# 105358-3SC002-01-A_IR.net
KiCad netlist of a schematic drawn in Altium Designer
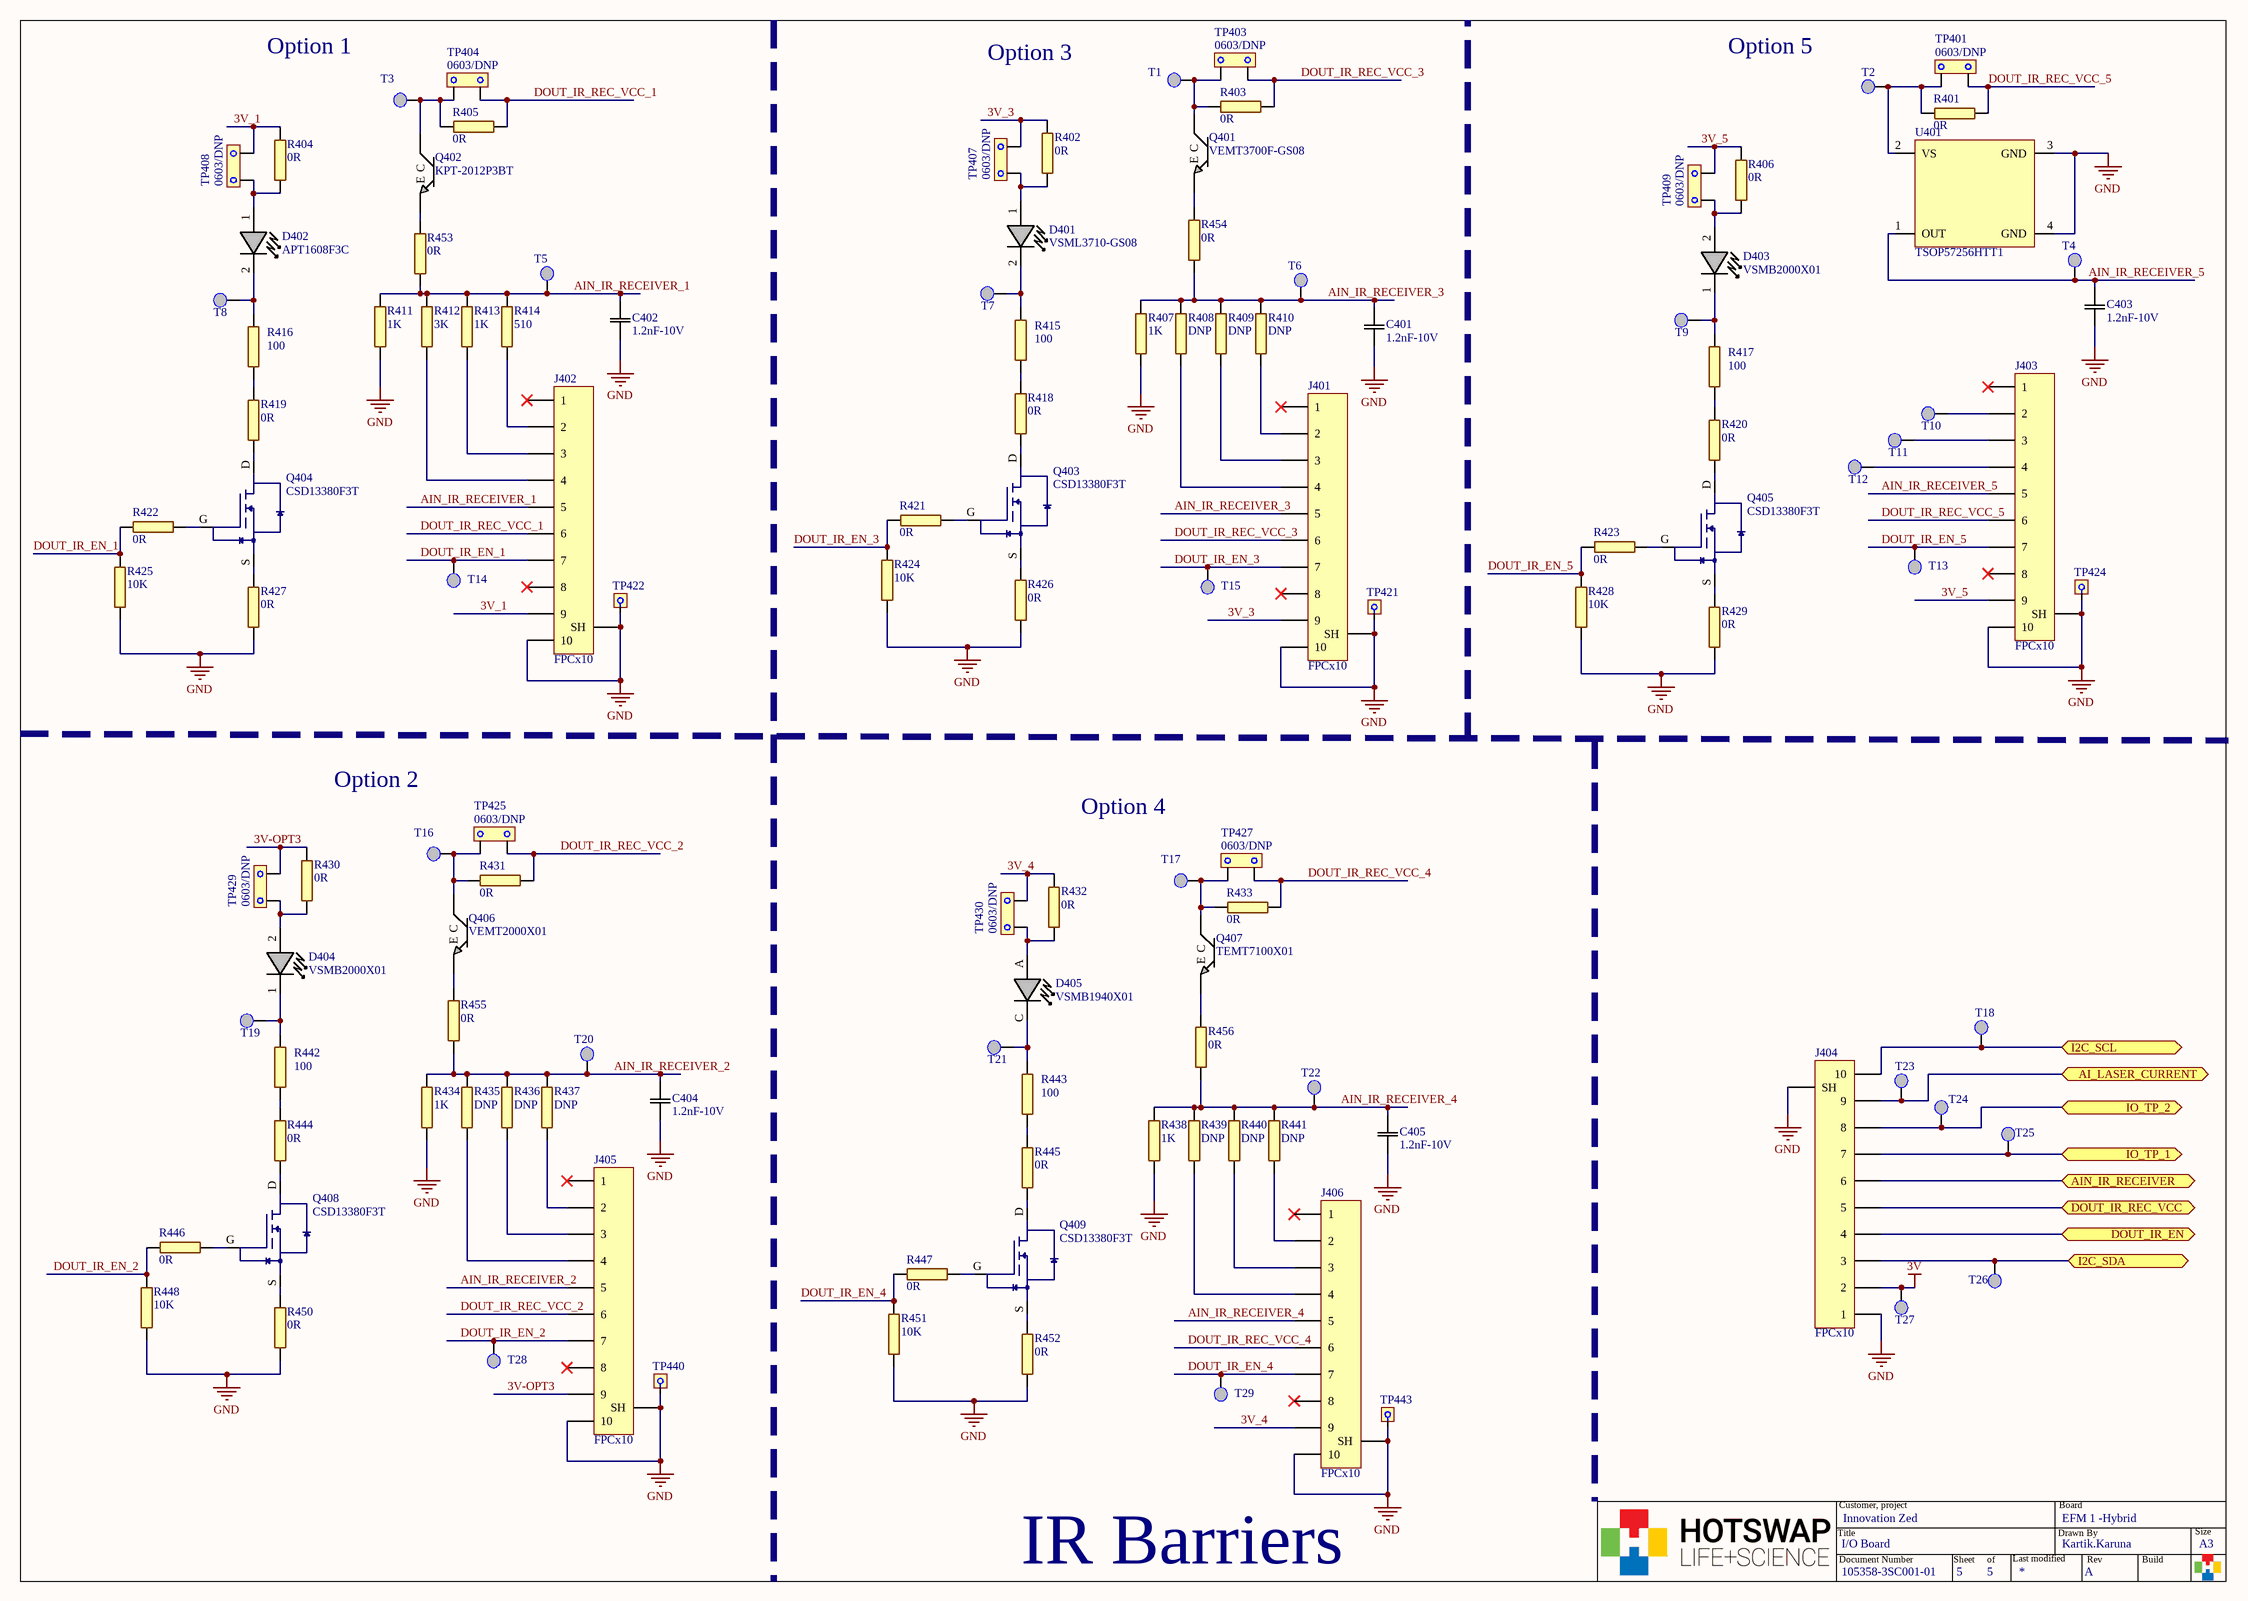
[diagram p0: 105358-3SC002-01-A_IR.SchDoc]

(export (version "E")
  (design (tool "Eeschema 10.0.6"))
  (components
    (comp (ref "C401")
      (value "1.2nF-10V")
      (footprint "0402C_HIGH_DENSITY")
      (description "1.2nF ±10% 10V U2J Ceramic Capacitor 0402")
      (fields
        (field (name "MANUFACTURER PART NUMBER") "GRM1557U1A122JA01D")
        (field (name "MANUFACTURER") "Murata Electronics North America")
      )
      (libsource (lib "ConnectMedical") (part "0402C-1.2nF-10V"))
    )
    (comp (ref "C402")
      (value "1.2nF-10V")
      (footprint "0402C_HIGH_DENSITY")
      (description "1.2nF ±10% 10V U2J Ceramic Capacitor 0402")
      (fields
        (field (name "MANUFACTURER PART NUMBER") "GRM1557U1A122JA01D")
        (field (name "MANUFACTURER") "Murata Electronics North America")
      )
      (libsource (lib "ConnectMedical") (part "0402C-1.2nF-10V"))
    )
    (comp (ref "C403")
      (value "1.2nF-10V")
      (footprint "0402C_HIGH_DENSITY")
      (description "1.2nF ±10% 10V U2J Ceramic Capacitor 0402")
      (fields
        (field (name "MANUFACTURER PART NUMBER") "GRM1557U1A122JA01D")
        (field (name "MANUFACTURER") "Murata Electronics North America")
      )
      (libsource (lib "ConnectMedical") (part "0402C-1.2nF-10V"))
    )
    (comp (ref "C404")
      (value "1.2nF-10V")
      (footprint "0402C_HIGH_DENSITY")
      (description "1.2nF ±10% 10V U2J Ceramic Capacitor 0402")
      (fields
        (field (name "MANUFACTURER PART NUMBER") "GRM1557U1A122JA01D")
        (field (name "MANUFACTURER") "Murata Electronics North America")
      )
      (libsource (lib "ConnectMedical") (part "0402C-1.2nF-10V"))
    )
    (comp (ref "C405")
      (value "1.2nF-10V")
      (footprint "0402C_HIGH_DENSITY")
      (description "1.2nF ±10% 10V U2J Ceramic Capacitor 0402")
      (fields
        (field (name "MANUFACTURER PART NUMBER") "GRM1557U1A122JA01D")
        (field (name "MANUFACTURER") "Murata Electronics North America")
      )
      (libsource (lib "ConnectMedical") (part "0402C-1.2nF-10V"))
    )
    (comp (ref "D401")
      (value "VSML3710-GS08")
      (footprint "VSML3710-GS08")
      (description "EMITTER IR 940NM 100MA PLCC")
      (fields
        (field (name "MANUFACTURER") "Vishay Semiconductor Opto Division")
        (field (name "DIGI-KEY PART NUMBER") "751-1257-1-ND")
      )
      (libsource (lib "ConnectMedical") (part "VSML3710-GS08"))
    )
    (comp (ref "D402")
      (value "APT1608F3C")
      (footprint "APT1608F3C")
      (description "0603 INFRARED DIODE")
      (fields
        (field (name "MANUFACTURER") "Kingbright")
        (field (name "DIGI-KEY PART NUMBER") "754-1433-1-ND")
      )
      (libsource (lib "ConnectMedical") (part "APT1608F3C"))
    )
    (comp (ref "D403")
      (value "VSMB2000X01")
      (footprint "SODFL580X160")
      (description "EMITTER IR 940NM 100MA SMD")
      (fields
        (field (name "MANUFACTURER") "Vishay Semiconductor Opto Division")
        (field (name "DIGI-KEY PART NUMBER") "VSMB2000X01CT-ND")
      )
      (libsource (lib "ConnectMedical") (part "VSMB2000X01"))
    )
    (comp (ref "D404")
      (value "VSMB2000X01")
      (footprint "SODFL580X160")
      (description "EMITTER IR 940NM 100MA SMD")
      (fields
        (field (name "MANUFACTURER") "Vishay Semiconductor Opto Division")
        (field (name "DIGI-KEY PART NUMBER") "VSMB2000X01CT-ND")
      )
      (libsource (lib "ConnectMedical") (part "VSMB2000X01"))
    )
    (comp (ref "D405")
      (value "VSMB1940X01")
      (footprint "VSMB1940X01")
      (description "EMITTER IR 940NM 100MA 0805")
      (fields
        (field (name "MANUFACTURER") "Vishay Semiconductor Opto Division")
        (field (name "DIGI-KEY PART NUMBER") "VSMB1940X01CT-ND")
      )
      (libsource (lib "ConnectMedical") (part "VSMB1940X01"))
    )
    (comp (ref "J401")
      (value "FPCx10")
      (footprint "FPCx10-5034801000")
      (description "CONN FFC FPC 10POS 0.50MM R/A")
      (fields
        (field (name "MANUFACTURER PART NUMBER") "5034801000")
        (field (name "MANUFACTURER") "Molex, LLC")
      )
      (libsource (lib "") (part "FPCx10_1"))
    )
    (comp (ref "J402")
      (value "FPCx10")
      (footprint "FPCx10-5034801000")
      (description "CONN FFC FPC 10POS 0.50MM R/A")
      (fields
        (field (name "MANUFACTURER PART NUMBER") "5034801000")
        (field (name "MANUFACTURER") "Molex, LLC")
      )
      (libsource (lib "") (part "FPCx10_1"))
    )
    (comp (ref "J403")
      (value "FPCx10")
      (footprint "FPCx10-5034801000")
      (description "CONN FFC FPC 10POS 0.50MM R/A")
      (fields
        (field (name "MANUFACTURER PART NUMBER") "5034801000")
        (field (name "MANUFACTURER") "Molex, LLC")
      )
      (libsource (lib "") (part "FPCx10_1"))
    )
    (comp (ref "J404")
      (value "FPCx10")
      (footprint "FPCx10-5034801000")
      (description "CONN FFC FPC 10POS 0.50MM R/A")
      (fields
        (field (name "MANUFACTURER PART NUMBER") "5034801000")
        (field (name "MANUFACTURER") "Molex, LLC")
      )
      (libsource (lib "ConnectMedical") (part "FPCx10"))
    )
    (comp (ref "J405")
      (value "FPCx10")
      (footprint "FPCx10-5034801000")
      (description "CONN FFC FPC 10POS 0.50MM R/A")
      (fields
        (field (name "MANUFACTURER PART NUMBER") "5034801000")
        (field (name "MANUFACTURER") "Molex, LLC")
      )
      (libsource (lib "") (part "FPCx10_1"))
    )
    (comp (ref "J406")
      (value "FPCx10")
      (footprint "FPCx10-5034801000")
      (description "CONN FFC FPC 10POS 0.50MM R/A")
      (fields
        (field (name "MANUFACTURER PART NUMBER") "5034801000")
        (field (name "MANUFACTURER") "Molex, LLC")
      )
      (libsource (lib "") (part "FPCx10_1"))
    )
    (comp (ref "Q401")
      (value "VEMT3700F-GS08")
      (footprint "VEMT3700F-GS08")
      (description "PHOTO TRANS. SMD PLCC2")
      (fields
        (field (name "MANUFACTURER") "Vishay Semiconductor Opto Division")
        (field (name "DIGI-KEY PART NUMBER") "VEMT3700F-GS08CT-ND")
      )
      (libsource (lib "ConnectMedical") (part "VEMT3700F-GS08"))
    )
    (comp (ref "Q402")
      (value "KPT-2012P3BT")
      (footprint "APT2012P3BT")
      (description "0805 PHOTOTRANSISTOR")
      (fields
        (field (name "MANUFACTURER") "Kingbright")
        (field (name "DIGI-KEY PART NUMBER") "754-1436-1-ND")
      )
      (libsource (lib "ConnectMedical") (part "APT2012P3BT"))
    )
    (comp (ref "Q403")
      (value "CSD13380F3T")
      (footprint "CSD13380F3-DFN40P69X35-3L")
      (description "12V N-CHANNEL FEMTOFET MOSFET")
      (fields (field (name "MANUFACTURER") "Texas Instruments"))
      (libsource (lib "ConnectMedical") (part "CSD13380F3T"))
    )
    (comp (ref "Q404")
      (value "CSD13380F3T")
      (footprint "CSD13380F3-DFN40P69X35-3L")
      (description "12V N-CHANNEL FEMTOFET MOSFET")
      (fields (field (name "MANUFACTURER") "Texas Instruments"))
      (libsource (lib "ConnectMedical") (part "CSD13380F3T"))
    )
    (comp (ref "Q405")
      (value "CSD13380F3T")
      (footprint "CSD13380F3-DFN40P69X35-3L")
      (description "12V N-CHANNEL FEMTOFET MOSFET")
      (fields (field (name "MANUFACTURER") "Texas Instruments"))
      (libsource (lib "ConnectMedical") (part "CSD13380F3T"))
    )
    (comp (ref "Q406")
      (value "VEMT2000X01")
      (footprint "SODFL580X160")
      (description "PHOTOTRANSISTOR NPN REV GULLWING")
      (fields
        (field (name "MANUFACTURER") "Vishay Semiconductor Opto Division")
        (field (name "DIGI-KEY PART NUMBER") "VEMT2000X01CT-ND")
      )
      (libsource (lib "ConnectMedical") (part "VEMT2000X01"))
    )
    (comp (ref "Q407")
      (value "TEMT7100X01")
      (footprint "TEMT7100X01")
      (description "PHOTOTRANSISTOR 870NM 0805 SMD")
      (fields
        (field (name "MANUFACTURER") "Vishay Semiconductor Opto Division")
        (field (name "DIGI-KEY PART NUMBER") "TEMT7100X01CT-ND")
      )
      (libsource (lib "ConnectMedical") (part "TEMT7100X01"))
    )
    (comp (ref "Q408")
      (value "CSD13380F3T")
      (footprint "CSD13380F3-DFN40P69X35-3L")
      (description "12V N-CHANNEL FEMTOFET MOSFET")
      (fields (field (name "MANUFACTURER") "Texas Instruments"))
      (libsource (lib "ConnectMedical") (part "CSD13380F3T"))
    )
    (comp (ref "Q409")
      (value "CSD13380F3T")
      (footprint "CSD13380F3-DFN40P69X35-3L")
      (description "12V N-CHANNEL FEMTOFET MOSFET")
      (fields (field (name "MANUFACTURER") "Texas Instruments"))
      (libsource (lib "ConnectMedical") (part "CSD13380F3T"))
    )
    (comp (ref "R401")
      (value "0R")
      (footprint "0603R-GENRIC")
      (description "RES SMD 0 OHM 1% 1/10W 0603")
      (fields (field (name "POWER") "0.063W"))
      (libsource (lib "ConnectMedical") (part "0603R-0R -1%-0.063W"))
    )
    (comp (ref "R402")
      (value "0R")
      (footprint "0603R-GENRIC")
      (description "RES SMD 0 OHM 1% 1/10W 0603")
      (fields (field (name "POWER") "0.063W"))
      (libsource (lib "") (part "0603R-0R -1%-0.063W_2"))
    )
    (comp (ref "R403")
      (value "0R")
      (footprint "0603R-GENRIC")
      (description "RES SMD 0 OHM 1% 1/10W 0603")
      (fields (field (name "POWER") "0.063W"))
      (libsource (lib "ConnectMedical") (part "0603R-0R -1%-0.063W"))
    )
    (comp (ref "R404")
      (value "0R")
      (footprint "0603R-GENRIC")
      (description "RES SMD 0 OHM 1% 1/10W 0603")
      (fields (field (name "POWER") "0.063W"))
      (libsource (lib "") (part "0603R-0R -1%-0.063W_2"))
    )
    (comp (ref "R405")
      (value "0R")
      (footprint "0603R-GENRIC")
      (description "RES SMD 0 OHM 1% 1/10W 0603")
      (fields (field (name "POWER") "0.063W"))
      (libsource (lib "ConnectMedical") (part "0603R-0R -1%-0.063W"))
    )
    (comp (ref "R406")
      (value "0R")
      (footprint "0603R-GENRIC")
      (description "RES SMD 0 OHM 1% 1/10W 0603")
      (fields (field (name "POWER") "0.063W"))
      (libsource (lib "") (part "0603R-0R -1%-0.063W_2"))
    )
    (comp (ref "R407")
      (value "1K")
      (footprint "0402R-GENERIC")
      (description "RES SMD 1kOHM 1% 1/16W 0402")
      (fields (field (name "TOLERANCE") "1%") (field (name "POWER") "0.063W"))
      (libsource (lib "ConnectMedical") (part "0402R-1k OHM-1%-0.063W"))
    )
    (comp (ref "R408")
      (value "DNP")
      (footprint "0603R-GENRIC")
      (description "RES 0603 DNP")
      (libsource (lib "ConnectMedical") (part "0603R_DNP"))
    )
    (comp (ref "R409")
      (value "DNP")
      (footprint "0603R-GENRIC")
      (description "RES 0603 DNP")
      (libsource (lib "ConnectMedical") (part "0603R_DNP"))
    )
    (comp (ref "R410")
      (value "DNP")
      (footprint "0603R-GENRIC")
      (description "RES 0603 DNP")
      (libsource (lib "ConnectMedical") (part "0603R_DNP"))
    )
    (comp (ref "R411")
      (value "1K")
      (footprint "0402R-GENERIC")
      (description "RES SMD 1kOHM 1% 1/16W 0402")
      (fields (field (name "TOLERANCE") "1%") (field (name "POWER") "0.063W"))
      (libsource (lib "ConnectMedical") (part "0402R-1k OHM-1%-0.063W"))
    )
    (comp (ref "R412")
      (value "3K")
      (footprint "0402R-GENERIC")
      (description "RES SMD 3kOHM 1% 1/16W 0402")
      (fields (field (name "TOLERANCE") "1%") (field (name "POWER") "0.063W"))
      (libsource (lib "ConnectMedical") (part "0402R-3k OHM-1%-0.063W"))
    )
    (comp (ref "R413")
      (value "1K")
      (footprint "0402R-GENERIC")
      (description "RES SMD 1kOHM 1% 1/16W 0402")
      (fields (field (name "TOLERANCE") "1%") (field (name "POWER") "0.063W"))
      (libsource (lib "ConnectMedical") (part "0402R-1k OHM-1%-0.063W"))
    )
    (comp (ref "R414")
      (value "510")
      (footprint "0402R-GENERIC")
      (description "RES SMD 100OHM 1% 1/16W 0402")
      (fields (field (name "TOLERANCE") "1%") (field (name "POWER") "0.063W"))
      (libsource (lib "ConnectMedical") (part "0402R-500 OHM-1%-0.063W"))
    )
    (comp (ref "R415")
      (value "100")
      (footprint "0402R-GENERIC")
      (description "RES SMD 100OHM 1% 1/16W 0402")
      (fields (field (name "DIGI-KEY PART NUMBER") "311-100LRCT-ND") (field (name "MANUFACTURER") "Yageo"))
      (libsource (lib "ConnectMedical") (part "0402R-100 OHM-1%-0.063W"))
    )
    (comp (ref "R416")
      (value "100")
      (footprint "0402R-GENERIC")
      (description "RES SMD 100OHM 1% 1/16W 0402")
      (fields (field (name "DIGI-KEY PART NUMBER") "311-100LRCT-ND") (field (name "MANUFACTURER") "Yageo"))
      (libsource (lib "ConnectMedical") (part "0402R-100 OHM-1%-0.063W"))
    )
    (comp (ref "R417")
      (value "100")
      (footprint "0402R-GENERIC")
      (description "RES SMD 100OHM 1% 1/16W 0402")
      (fields (field (name "DIGI-KEY PART NUMBER") "311-100LRCT-ND") (field (name "MANUFACTURER") "Yageo"))
      (libsource (lib "ConnectMedical") (part "0402R-100 OHM-1%-0.063W"))
    )
    (comp (ref "R418")
      (value "0R")
      (footprint "0603R-GENRIC")
      (description "RES SMD 0 OHM 1% 1/10W 0603")
      (fields (field (name "POWER") "0.063W"))
      (libsource (lib "") (part "0603R-0R -1%-0.063W_1"))
    )
    (comp (ref "R419")
      (value "0R")
      (footprint "0603R-GENRIC")
      (description "RES SMD 0 OHM 1% 1/10W 0603")
      (fields (field (name "POWER") "0.063W"))
      (libsource (lib "") (part "0603R-0R -1%-0.063W_1"))
    )
    (comp (ref "R420")
      (value "0R")
      (footprint "0603R-GENRIC")
      (description "RES SMD 0 OHM 1% 1/10W 0603")
      (fields (field (name "POWER") "0.063W"))
      (libsource (lib "") (part "0603R-0R -1%-0.063W_1"))
    )
    (comp (ref "R421")
      (value "0R")
      (footprint "0603R-GENRIC")
      (description "RES SMD 0 OHM 1% 1/10W 0603")
      (fields (field (name "POWER") "0.063W"))
      (libsource (lib "ConnectMedical") (part "0603R-0R -1%-0.063W"))
    )
    (comp (ref "R422")
      (value "0R")
      (footprint "0603R-GENRIC")
      (description "RES SMD 0 OHM 1% 1/10W 0603")
      (fields (field (name "POWER") "0.063W"))
      (libsource (lib "ConnectMedical") (part "0603R-0R -1%-0.063W"))
    )
    (comp (ref "R423")
      (value "0R")
      (footprint "0603R-GENRIC")
      (description "RES SMD 0 OHM 1% 1/10W 0603")
      (fields (field (name "POWER") "0.063W"))
      (libsource (lib "ConnectMedical") (part "0603R-0R -1%-0.063W"))
    )
    (comp (ref "R424")
      (value "10K")
      (footprint "0402R-GENERIC")
      (description "RES SMD 10kOHM 1% 1/16W 0402")
      (fields (field (name "DIGI-KEY PART NUMBER") "311-10.0KLRCT-ND") (field (name "MANUFACTURER") "Yageo"))
      (libsource (lib "ConnectMedical") (part "0402R-10k OHM-1%-0.063W"))
    )
    (comp (ref "R425")
      (value "10K")
      (footprint "0402R-GENERIC")
      (description "RES SMD 10kOHM 1% 1/16W 0402")
      (fields (field (name "DIGI-KEY PART NUMBER") "311-10.0KLRCT-ND") (field (name "MANUFACTURER") "Yageo"))
      (libsource (lib "ConnectMedical") (part "0402R-10k OHM-1%-0.063W"))
    )
    (comp (ref "R426")
      (value "0R")
      (footprint "0603R-GENRIC")
      (description "RES SMD 0 OHM 1% 1/10W 0603")
      (fields (field (name "POWER") "0.063W"))
      (libsource (lib "") (part "0603R-0R -1%-0.063W_2"))
    )
    (comp (ref "R427")
      (value "0R")
      (footprint "0603R-GENRIC")
      (description "RES SMD 0 OHM 1% 1/10W 0603")
      (fields (field (name "POWER") "0.063W"))
      (libsource (lib "") (part "0603R-0R -1%-0.063W_2"))
    )
    (comp (ref "R428")
      (value "10K")
      (footprint "0402R-GENERIC")
      (description "RES SMD 10kOHM 1% 1/16W 0402")
      (fields (field (name "DIGI-KEY PART NUMBER") "311-10.0KLRCT-ND") (field (name "MANUFACTURER") "Yageo"))
      (libsource (lib "ConnectMedical") (part "0402R-10k OHM-1%-0.063W"))
    )
    (comp (ref "R429")
      (value "0R")
      (footprint "0603R-GENRIC")
      (description "RES SMD 0 OHM 1% 1/10W 0603")
      (fields (field (name "POWER") "0.063W"))
      (libsource (lib "") (part "0603R-0R -1%-0.063W_2"))
    )
    (comp (ref "R430")
      (value "0R")
      (footprint "0603R-GENRIC")
      (description "RES SMD 0 OHM 1% 1/10W 0603")
      (fields (field (name "POWER") "0.063W"))
      (libsource (lib "") (part "0603R-0R -1%-0.063W_2"))
    )
    (comp (ref "R431")
      (value "0R")
      (footprint "0603R-GENRIC")
      (description "RES SMD 0 OHM 1% 1/10W 0603")
      (fields (field (name "POWER") "0.063W"))
      (libsource (lib "ConnectMedical") (part "0603R-0R -1%-0.063W"))
    )
    (comp (ref "R432")
      (value "0R")
      (footprint "0603R-GENRIC")
      (description "RES SMD 0 OHM 1% 1/10W 0603")
      (fields (field (name "POWER") "0.063W"))
      (libsource (lib "") (part "0603R-0R -1%-0.063W_2"))
    )
    (comp (ref "R433")
      (value "0R")
      (footprint "0603R-GENRIC")
      (description "RES SMD 0 OHM 1% 1/10W 0603")
      (fields (field (name "POWER") "0.063W"))
      (libsource (lib "ConnectMedical") (part "0603R-0R -1%-0.063W"))
    )
    (comp (ref "R434")
      (value "1K")
      (footprint "0402R-GENERIC")
      (description "RES SMD 1kOHM 1% 1/16W 0402")
      (fields (field (name "TOLERANCE") "1%") (field (name "POWER") "0.063W"))
      (libsource (lib "ConnectMedical") (part "0402R-1k OHM-1%-0.063W"))
    )
    (comp (ref "R435")
      (value "DNP")
      (footprint "0603R-GENRIC")
      (description "RES 0603 DNP")
      (libsource (lib "ConnectMedical") (part "0603R_DNP"))
    )
    (comp (ref "R436")
      (value "DNP")
      (footprint "0603R-GENRIC")
      (description "RES 0603 DNP")
      (libsource (lib "ConnectMedical") (part "0603R_DNP"))
    )
    (comp (ref "R437")
      (value "DNP")
      (footprint "0603R-GENRIC")
      (description "RES 0603 DNP")
      (libsource (lib "ConnectMedical") (part "0603R_DNP"))
    )
    (comp (ref "R438")
      (value "1K")
      (footprint "0402R-GENERIC")
      (description "RES SMD 1kOHM 1% 1/16W 0402")
      (fields (field (name "TOLERANCE") "1%") (field (name "POWER") "0.063W"))
      (libsource (lib "ConnectMedical") (part "0402R-1k OHM-1%-0.063W"))
    )
    (comp (ref "R439")
      (value "DNP")
      (footprint "0603R-GENRIC")
      (description "RES 0603 DNP")
      (libsource (lib "ConnectMedical") (part "0603R_DNP"))
    )
    (comp (ref "R440")
      (value "DNP")
      (footprint "0603R-GENRIC")
      (description "RES 0603 DNP")
      (libsource (lib "ConnectMedical") (part "0603R_DNP"))
    )
    (comp (ref "R441")
      (value "DNP")
      (footprint "0603R-GENRIC")
      (description "RES 0603 DNP")
      (libsource (lib "ConnectMedical") (part "0603R_DNP"))
    )
    (comp (ref "R442")
      (value "100")
      (footprint "0402R-GENERIC")
      (description "RES SMD 100OHM 1% 1/16W 0402")
      (fields (field (name "DIGI-KEY PART NUMBER") "311-100LRCT-ND") (field (name "MANUFACTURER") "Yageo"))
      (libsource (lib "ConnectMedical") (part "0402R-100 OHM-1%-0.063W"))
    )
    (comp (ref "R443")
      (value "100")
      (footprint "0402R-GENERIC")
      (description "RES SMD 100OHM 1% 1/16W 0402")
      (fields (field (name "DIGI-KEY PART NUMBER") "311-100LRCT-ND") (field (name "MANUFACTURER") "Yageo"))
      (libsource (lib "ConnectMedical") (part "0402R-100 OHM-1%-0.063W"))
    )
    (comp (ref "R444")
      (value "0R")
      (footprint "0603R-GENRIC")
      (description "RES SMD 0 OHM 1% 1/10W 0603")
      (fields (field (name "POWER") "0.063W"))
      (libsource (lib "") (part "0603R-0R -1%-0.063W_1"))
    )
    (comp (ref "R445")
      (value "0R")
      (footprint "0603R-GENRIC")
      (description "RES SMD 0 OHM 1% 1/10W 0603")
      (fields (field (name "POWER") "0.063W"))
      (libsource (lib "") (part "0603R-0R -1%-0.063W_1"))
    )
    (comp (ref "R446")
      (value "0R")
      (footprint "0603R-GENRIC")
      (description "RES SMD 0 OHM 1% 1/10W 0603")
      (fields (field (name "POWER") "0.063W"))
      (libsource (lib "ConnectMedical") (part "0603R-0R -1%-0.063W"))
    )
    (comp (ref "R447")
      (value "0R")
      (footprint "0603R-GENRIC")
      (description "RES SMD 0 OHM 1% 1/10W 0603")
      (fields (field (name "POWER") "0.063W"))
      (libsource (lib "ConnectMedical") (part "0603R-0R -1%-0.063W"))
    )
    (comp (ref "R448")
      (value "10K")
      (footprint "0402R-GENERIC")
      (description "RES SMD 10kOHM 1% 1/16W 0402")
      (fields (field (name "DIGI-KEY PART NUMBER") "311-10.0KLRCT-ND") (field (name "MANUFACTURER") "Yageo"))
      (libsource (lib "ConnectMedical") (part "0402R-10k OHM-1%-0.063W"))
    )
    (comp (ref "R450")
      (value "0R")
      (footprint "0603R-GENRIC")
      (description "RES SMD 0 OHM 1% 1/10W 0603")
      (fields (field (name "POWER") "0.063W"))
      (libsource (lib "") (part "0603R-0R -1%-0.063W_2"))
    )
    (comp (ref "R451")
      (value "10K")
      (footprint "0402R-GENERIC")
      (description "RES SMD 10kOHM 1% 1/16W 0402")
      (fields (field (name "DIGI-KEY PART NUMBER") "311-10.0KLRCT-ND") (field (name "MANUFACTURER") "Yageo"))
      (libsource (lib "ConnectMedical") (part "0402R-10k OHM-1%-0.063W"))
    )
    (comp (ref "R452")
      (value "0R")
      (footprint "0603R-GENRIC")
      (description "RES SMD 0 OHM 1% 1/10W 0603")
      (fields (field (name "POWER") "0.063W"))
      (libsource (lib "") (part "0603R-0R -1%-0.063W_2"))
    )
    (comp (ref "R453")
      (value "0R")
      (footprint "0603R-GENRIC")
      (description "RES SMD 0 OHM 1% 1/10W 0603")
      (fields (field (name "POWER") "0.063W"))
      (libsource (lib "") (part "0603R-0R -1%-0.063W_1"))
    )
    (comp (ref "R454")
      (value "0R")
      (footprint "0603R-GENRIC")
      (description "RES SMD 0 OHM 1% 1/10W 0603")
      (fields (field (name "POWER") "0.063W"))
      (libsource (lib "") (part "0603R-0R -1%-0.063W_1"))
    )
    (comp (ref "R455")
      (value "0R")
      (footprint "0603R-GENRIC")
      (description "RES SMD 0 OHM 1% 1/10W 0603")
      (fields (field (name "POWER") "0.063W"))
      (libsource (lib "") (part "0603R-0R -1%-0.063W_1"))
    )
    (comp (ref "R456")
      (value "0R")
      (footprint "0603R-GENRIC")
      (description "RES SMD 0 OHM 1% 1/10W 0603")
      (fields (field (name "POWER") "0.063W"))
      (libsource (lib "") (part "0603R-0R -1%-0.063W_1"))
    )
    (comp (ref "T1")
      (value "TEST POINT")
      (footprint "PAD TEST POINT")
      (description "Testing Poiny")
      (libsource (lib "ConnectMedical") (part "TEST POINT"))
    )
    (comp (ref "T2")
      (value "TEST POINT")
      (footprint "PAD TEST POINT")
      (description "Testing Poiny")
      (libsource (lib "ConnectMedical") (part "TEST POINT"))
    )
    (comp (ref "T3")
      (value "TEST POINT")
      (footprint "PAD TEST POINT")
      (description "Testing Poiny")
      (libsource (lib "ConnectMedical") (part "TEST POINT"))
    )
    (comp (ref "T4")
      (value "TEST POINT")
      (footprint "PAD TEST POINT")
      (description "Testing Poiny")
      (libsource (lib "ConnectMedical") (part "TEST POINT"))
    )
    (comp (ref "T5")
      (value "TEST POINT")
      (footprint "PAD TEST POINT")
      (description "Testing Poiny")
      (libsource (lib "ConnectMedical") (part "TEST POINT"))
    )
    (comp (ref "T6")
      (value "TEST POINT")
      (footprint "PAD TEST POINT")
      (description "Testing Poiny")
      (libsource (lib "ConnectMedical") (part "TEST POINT"))
    )
    (comp (ref "T7")
      (value "TEST POINT")
      (footprint "PAD TEST POINT")
      (description "Testing Poiny")
      (libsource (lib "ConnectMedical") (part "TEST POINT"))
    )
    (comp (ref "T8")
      (value "TEST POINT")
      (footprint "PAD TEST POINT")
      (description "Testing Poiny")
      (libsource (lib "ConnectMedical") (part "TEST POINT"))
    )
    (comp (ref "T9")
      (value "TEST POINT")
      (footprint "PAD TEST POINT")
      (description "Testing Poiny")
      (libsource (lib "ConnectMedical") (part "TEST POINT"))
    )
    (comp (ref "T10")
      (value "TEST POINT")
      (footprint "PAD TEST POINT")
      (description "Testing Poiny")
      (libsource (lib "ConnectMedical") (part "TEST POINT"))
    )
    (comp (ref "T11")
      (value "TEST POINT")
      (footprint "PAD TEST POINT")
      (description "Testing Poiny")
      (libsource (lib "ConnectMedical") (part "TEST POINT"))
    )
    (comp (ref "T12")
      (value "TEST POINT")
      (footprint "PAD TEST POINT")
      (description "Testing Poiny")
      (libsource (lib "ConnectMedical") (part "TEST POINT"))
    )
    (comp (ref "T13")
      (value "TEST POINT")
      (footprint "PAD TEST POINT")
      (description "Testing Poiny")
      (libsource (lib "ConnectMedical") (part "TEST POINT"))
    )
    (comp (ref "T14")
      (value "TEST POINT")
      (footprint "PAD TEST POINT")
      (description "Testing Poiny")
      (libsource (lib "ConnectMedical") (part "TEST POINT"))
    )
    (comp (ref "T15")
      (value "TEST POINT")
      (footprint "PAD TEST POINT")
      (description "Testing Poiny")
      (libsource (lib "ConnectMedical") (part "TEST POINT"))
    )
    (comp (ref "T16")
      (value "TEST POINT")
      (footprint "PAD TEST POINT")
      (description "Testing Poiny")
      (libsource (lib "ConnectMedical") (part "TEST POINT"))
    )
    (comp (ref "T17")
      (value "TEST POINT")
      (footprint "PAD TEST POINT")
      (description "Testing Poiny")
      (libsource (lib "ConnectMedical") (part "TEST POINT"))
    )
    (comp (ref "T18")
      (value "TEST POINT")
      (footprint "PAD TEST POINT")
      (description "Testing Poiny")
      (libsource (lib "ConnectMedical") (part "TEST POINT"))
    )
    (comp (ref "T19")
      (value "TEST POINT")
      (footprint "PAD TEST POINT")
      (description "Testing Poiny")
      (libsource (lib "ConnectMedical") (part "TEST POINT"))
    )
    (comp (ref "T20")
      (value "TEST POINT")
      (footprint "PAD TEST POINT")
      (description "Testing Poiny")
      (libsource (lib "ConnectMedical") (part "TEST POINT"))
    )
    (comp (ref "T21")
      (value "TEST POINT")
      (footprint "PAD TEST POINT")
      (description "Testing Poiny")
      (libsource (lib "ConnectMedical") (part "TEST POINT"))
    )
    (comp (ref "T22")
      (value "TEST POINT")
      (footprint "PAD TEST POINT")
      (description "Testing Poiny")
      (libsource (lib "ConnectMedical") (part "TEST POINT"))
    )
    (comp (ref "T23")
      (value "TEST POINT")
      (footprint "PAD TEST POINT")
      (description "Testing Poiny")
      (libsource (lib "ConnectMedical") (part "TEST POINT"))
    )
    (comp (ref "T24")
      (value "TEST POINT")
      (footprint "PAD TEST POINT")
      (description "Testing Poiny")
      (libsource (lib "ConnectMedical") (part "TEST POINT"))
    )
    (comp (ref "T25")
      (value "TEST POINT")
      (footprint "PAD TEST POINT")
      (description "Testing Poiny")
      (libsource (lib "ConnectMedical") (part "TEST POINT"))
    )
    (comp (ref "T26")
      (value "TEST POINT")
      (footprint "PAD TEST POINT")
      (description "Testing Poiny")
      (libsource (lib "ConnectMedical") (part "TEST POINT"))
    )
    (comp (ref "T27")
      (value "TEST POINT")
      (footprint "PAD TEST POINT")
      (description "Testing Poiny")
      (libsource (lib "ConnectMedical") (part "TEST POINT"))
    )
    (comp (ref "T28")
      (value "TEST POINT")
      (footprint "PAD TEST POINT")
      (description "Testing Poiny")
      (libsource (lib "ConnectMedical") (part "TEST POINT"))
    )
    (comp (ref "T29")
      (value "TEST POINT")
      (footprint "PAD TEST POINT")
      (description "Testing Poiny")
      (libsource (lib "ConnectMedical") (part "TEST POINT"))
    )
    (comp (ref "TP401")
      (value "0603/DNP")
      (footprint "TESTPOINT_C_R0608")
      (description "Test point for Med Current 0402 JUMPER SMD O OHM 1% 1/4W 0603")
      (libsource (lib "ConnectMedical") (part "TP_C_R0603"))
    )
    (comp (ref "TP403")
      (value "0603/DNP")
      (footprint "TESTPOINT_C_R0608")
      (description "Test point for Med Current 0402 JUMPER SMD O OHM 1% 1/4W 0603")
      (libsource (lib "ConnectMedical") (part "TP_C_R0603"))
    )
    (comp (ref "TP404")
      (value "0603/DNP")
      (footprint "TESTPOINT_C_R0608")
      (description "Test point for Med Current 0402 JUMPER SMD O OHM 1% 1/4W 0603")
      (libsource (lib "ConnectMedical") (part "TP_C_R0603"))
    )
    (comp (ref "TP407")
      (value "0603/DNP")
      (footprint "TESTPOINT_C_R0608")
      (description "Test point for Med Current 0402 JUMPER SMD O OHM 1% 1/4W 0603")
      (libsource (lib "") (part "TP_C_R0603_1"))
    )
    (comp (ref "TP408")
      (value "0603/DNP")
      (footprint "TESTPOINT_C_R0608")
      (description "Test point for Med Current 0402 JUMPER SMD O OHM 1% 1/4W 0603")
      (libsource (lib "") (part "TP_C_R0603_1"))
    )
    (comp (ref "TP409")
      (value "0603/DNP")
      (footprint "TESTPOINT_C_R0608")
      (description "Test point for Med Current 0402 JUMPER SMD O OHM 1% 1/4W 0603")
      (libsource (lib "") (part "TP_C_R0603_1"))
    )
    (comp (ref "TP421")
      (value "TP_V_HOOK")
      (footprint "Testpoint_Hook")
      (description "Black PC Test Point")
      (fields
        (field (name "DIGI-KEY PART NUMBER") "36-5001-ND")
        (field (name "MANUFACTURER") "Keystone Electronics")
      )
      (libsource (lib "ConnectMedical") (part "TP_V_HOOK"))
    )
    (comp (ref "TP422")
      (value "TP_V_HOOK")
      (footprint "Testpoint_Hook")
      (description "Black PC Test Point")
      (fields
        (field (name "DIGI-KEY PART NUMBER") "36-5001-ND")
        (field (name "MANUFACTURER") "Keystone Electronics")
      )
      (libsource (lib "ConnectMedical") (part "TP_V_HOOK"))
    )
    (comp (ref "TP424")
      (value "TP_V_HOOK")
      (footprint "Testpoint_Hook")
      (description "Black PC Test Point")
      (fields
        (field (name "DIGI-KEY PART NUMBER") "36-5001-ND")
        (field (name "MANUFACTURER") "Keystone Electronics")
      )
      (libsource (lib "ConnectMedical") (part "TP_V_HOOK"))
    )
    (comp (ref "TP425")
      (value "0603/DNP")
      (footprint "TESTPOINT_C_R0608")
      (description "Test point for Med Current 0402 JUMPER SMD O OHM 1% 1/4W 0603")
      (libsource (lib "ConnectMedical") (part "TP_C_R0603"))
    )
    (comp (ref "TP427")
      (value "0603/DNP")
      (footprint "TESTPOINT_C_R0608")
      (description "Test point for Med Current 0402 JUMPER SMD O OHM 1% 1/4W 0603")
      (libsource (lib "ConnectMedical") (part "TP_C_R0603"))
    )
    (comp (ref "TP429")
      (value "0603/DNP")
      (footprint "TESTPOINT_C_R0608")
      (description "Test point for Med Current 0402 JUMPER SMD O OHM 1% 1/4W 0603")
      (libsource (lib "") (part "TP_C_R0603_1"))
    )
    (comp (ref "TP430")
      (value "0603/DNP")
      (footprint "TESTPOINT_C_R0608")
      (description "Test point for Med Current 0402 JUMPER SMD O OHM 1% 1/4W 0603")
      (libsource (lib "") (part "TP_C_R0603_1"))
    )
    (comp (ref "TP440")
      (value "TP_V_HOOK")
      (footprint "Testpoint_Hook")
      (description "Black PC Test Point")
      (fields
        (field (name "DIGI-KEY PART NUMBER") "36-5001-ND")
        (field (name "MANUFACTURER") "Keystone Electronics")
      )
      (libsource (lib "ConnectMedical") (part "TP_V_HOOK"))
    )
    (comp (ref "TP443")
      (value "TP_V_HOOK")
      (footprint "Testpoint_Hook")
      (description "Black PC Test Point")
      (fields
        (field (name "DIGI-KEY PART NUMBER") "36-5001-ND")
        (field (name "MANUFACTURER") "Keystone Electronics")
      )
      (libsource (lib "ConnectMedical") (part "TP_V_HOOK"))
    )
    (comp (ref "U401")
      (value "TSOP57256HTT1")
      (footprint "TSOP57256HTT1")
      (description "MOD IR RCVR 56KHZ TOP VIEW SHIEL")
      (fields
        (field (name "MANUFACTURER") "Vishay Semiconductor Opto Division")
        (field (name "DIGI-KEY PART NUMBER") "TSOP57256HTT1-ND")
      )
      (libsource (lib "ConnectMedical") (part "TSOP57256HTT1"))
    )
  )
  (nets
    (net (code "1") (name "/3V-OPT3") (class "Default")
      (node (ref "J405") (pin "9") (pinfunction "9_9") (pintype "passive"))
      (node (ref "R430") (pin "2") (pintype "passive"))
      (node (ref "TP429") (pin "2") (pintype "power_in"))
    )
    (net (code "2") (name "/3V_1") (class "Default")
      (node (ref "J402") (pin "9") (pinfunction "9_9") (pintype "passive"))
      (node (ref "R404") (pin "2") (pintype "passive"))
      (node (ref "TP408") (pin "2") (pintype "power_in"))
    )
    (net (code "3") (name "/3V_3") (class "Default")
      (node (ref "J401") (pin "9") (pinfunction "9_9") (pintype "passive"))
      (node (ref "R402") (pin "2") (pintype "passive"))
      (node (ref "TP407") (pin "2") (pintype "power_in"))
    )
    (net (code "4") (name "/3V_4") (class "Default")
      (node (ref "J406") (pin "9") (pinfunction "9_9") (pintype "passive"))
      (node (ref "R432") (pin "2") (pintype "passive"))
      (node (ref "TP430") (pin "2") (pintype "power_in"))
    )
    (net (code "5") (name "/3V_5") (class "Default")
      (node (ref "J403") (pin "9") (pinfunction "9_9") (pintype "passive"))
      (node (ref "R406") (pin "2") (pintype "passive"))
      (node (ref "TP409") (pin "2") (pintype "power_in"))
    )
    (net (code "6") (name "/AIN_IR_RECEIVER") (class "Default")
      (node (ref "J404") (pin "6") (pinfunction "6_6") (pintype "passive"))
    )
    (net (code "7") (name "/AIN_IR_RECEIVER_1") (class "Default")
      (node (ref "C402") (pin "2") (pinfunction "2_2") (pintype "passive"))
      (node (ref "J402") (pin "5") (pinfunction "5_5") (pintype "passive"))
      (node (ref "R411") (pin "1") (pintype "passive"))
      (node (ref "R412") (pin "1") (pintype "passive"))
      (node (ref "R413") (pin "1") (pintype "passive"))
      (node (ref "R414") (pin "1") (pintype "passive"))
      (node (ref "R453") (pin "2") (pintype "passive"))
      (node (ref "T5") (pin "1") (pinfunction "Test_Point_1") (pintype "passive"))
    )
    (net (code "8") (name "/AIN_IR_RECEIVER_2") (class "Default")
      (node (ref "C404") (pin "2") (pinfunction "2_2") (pintype "passive"))
      (node (ref "J405") (pin "5") (pinfunction "5_5") (pintype "passive"))
      (node (ref "R434") (pin "1") (pintype "passive"))
      (node (ref "R435") (pin "1") (pintype "passive"))
      (node (ref "R436") (pin "1") (pintype "passive"))
      (node (ref "R437") (pin "1") (pintype "passive"))
      (node (ref "R455") (pin "2") (pintype "passive"))
      (node (ref "T20") (pin "1") (pinfunction "Test_Point_1") (pintype "passive"))
    )
    (net (code "9") (name "/AIN_IR_RECEIVER_3") (class "Default")
      (node (ref "C401") (pin "2") (pinfunction "2_2") (pintype "passive"))
      (node (ref "J401") (pin "5") (pinfunction "5_5") (pintype "passive"))
      (node (ref "R407") (pin "1") (pintype "passive"))
      (node (ref "R408") (pin "1") (pintype "passive"))
      (node (ref "R409") (pin "1") (pintype "passive"))
      (node (ref "R410") (pin "1") (pintype "passive"))
      (node (ref "R454") (pin "2") (pintype "passive"))
      (node (ref "T6") (pin "1") (pinfunction "Test_Point_1") (pintype "passive"))
    )
    (net (code "10") (name "/AIN_IR_RECEIVER_4") (class "Default")
      (node (ref "C405") (pin "2") (pinfunction "2_2") (pintype "passive"))
      (node (ref "J406") (pin "5") (pinfunction "5_5") (pintype "passive"))
      (node (ref "R438") (pin "1") (pintype "passive"))
      (node (ref "R439") (pin "1") (pintype "passive"))
      (node (ref "R440") (pin "1") (pintype "passive"))
      (node (ref "R441") (pin "1") (pintype "passive"))
      (node (ref "R456") (pin "2") (pintype "passive"))
      (node (ref "T22") (pin "1") (pinfunction "Test_Point_1") (pintype "passive"))
    )
    (net (code "11") (name "/AIN_IR_RECEIVER_5") (class "Default")
      (node (ref "C403") (pin "2") (pinfunction "2_2") (pintype "passive"))
      (node (ref "J403") (pin "5") (pinfunction "5_5") (pintype "passive"))
      (node (ref "T4") (pin "1") (pinfunction "Test_Point_1") (pintype "passive"))
      (node (ref "U401") (pin "1") (pinfunction "OUT_1") (pintype "power_in"))
    )
    (net (code "12") (name "/AI_LASER_CURRENT") (class "Default")
      (node (ref "J404") (pin "9") (pinfunction "9_9") (pintype "passive"))
      (node (ref "T23") (pin "1") (pinfunction "Test_Point_1") (pintype "passive"))
    )
    (net (code "13") (name "/DOUT_IR_EN") (class "Default")
      (node (ref "J404") (pin "4") (pinfunction "4_4") (pintype "passive"))
    )
    (net (code "14") (name "/DOUT_IR_EN_1") (class "Default")
      (node (ref "J402") (pin "7") (pinfunction "7_7") (pintype "passive"))
      (node (ref "R422") (pin "1") (pintype "passive"))
      (node (ref "R425") (pin "1") (pintype "passive"))
      (node (ref "T14") (pin "1") (pinfunction "Test_Point_1") (pintype "passive"))
    )
    (net (code "15") (name "/DOUT_IR_EN_2") (class "Default")
      (node (ref "J405") (pin "7") (pinfunction "7_7") (pintype "passive"))
      (node (ref "R446") (pin "1") (pintype "passive"))
      (node (ref "R448") (pin "1") (pintype "passive"))
      (node (ref "T28") (pin "1") (pinfunction "Test_Point_1") (pintype "passive"))
    )
    (net (code "16") (name "/DOUT_IR_EN_3") (class "Default")
      (node (ref "J401") (pin "7") (pinfunction "7_7") (pintype "passive"))
      (node (ref "R421") (pin "1") (pintype "passive"))
      (node (ref "R424") (pin "1") (pintype "passive"))
      (node (ref "T15") (pin "1") (pinfunction "Test_Point_1") (pintype "passive"))
    )
    (net (code "17") (name "/DOUT_IR_EN_4") (class "Default")
      (node (ref "J406") (pin "7") (pinfunction "7_7") (pintype "passive"))
      (node (ref "R447") (pin "1") (pintype "passive"))
      (node (ref "R451") (pin "1") (pintype "passive"))
      (node (ref "T29") (pin "1") (pinfunction "Test_Point_1") (pintype "passive"))
    )
    (net (code "18") (name "/DOUT_IR_EN_5") (class "Default")
      (node (ref "J403") (pin "7") (pinfunction "7_7") (pintype "passive"))
      (node (ref "R423") (pin "1") (pintype "passive"))
      (node (ref "R428") (pin "1") (pintype "passive"))
      (node (ref "T13") (pin "1") (pinfunction "Test_Point_1") (pintype "passive"))
    )
    (net (code "19") (name "/DOUT_IR_REC_VCC") (class "Default")
      (node (ref "J404") (pin "5") (pinfunction "5_5") (pintype "passive"))
    )
    (net (code "20") (name "/DOUT_IR_REC_VCC_1") (class "Default")
      (node (ref "J402") (pin "6") (pinfunction "6_6") (pintype "passive"))
      (node (ref "R405") (pin "2") (pintype "passive"))
      (node (ref "TP404") (pin "2") (pintype "power_in"))
    )
    (net (code "21") (name "/DOUT_IR_REC_VCC_2") (class "Default")
      (node (ref "J405") (pin "6") (pinfunction "6_6") (pintype "passive"))
      (node (ref "R431") (pin "2") (pintype "passive"))
      (node (ref "TP425") (pin "2") (pintype "power_in"))
    )
    (net (code "22") (name "/DOUT_IR_REC_VCC_3") (class "Default")
      (node (ref "J401") (pin "6") (pinfunction "6_6") (pintype "passive"))
      (node (ref "R403") (pin "2") (pintype "passive"))
      (node (ref "TP403") (pin "2") (pintype "power_in"))
    )
    (net (code "23") (name "/DOUT_IR_REC_VCC_4") (class "Default")
      (node (ref "J406") (pin "6") (pinfunction "6_6") (pintype "passive"))
      (node (ref "R433") (pin "2") (pintype "passive"))
      (node (ref "TP427") (pin "2") (pintype "power_in"))
    )
    (net (code "24") (name "/DOUT_IR_REC_VCC_5") (class "Default")
      (node (ref "J403") (pin "6") (pinfunction "6_6") (pintype "passive"))
      (node (ref "R401") (pin "2") (pintype "passive"))
      (node (ref "TP401") (pin "2") (pintype "power_in"))
    )
    (net (code "25") (name "/I2C_SCL") (class "Default")
      (node (ref "J404") (pin "10") (pinfunction "10_10") (pintype "passive"))
      (node (ref "T18") (pin "1") (pinfunction "Test_Point_1") (pintype "passive"))
    )
    (net (code "26") (name "/I2C_SDA") (class "Default")
      (node (ref "J404") (pin "3") (pinfunction "3_3") (pintype "passive"))
      (node (ref "T26") (pin "1") (pinfunction "Test_Point_1") (pintype "passive"))
    )
    (net (code "27") (name "/IO_TP_1") (class "Default")
      (node (ref "J404") (pin "7") (pinfunction "7_7") (pintype "passive"))
      (node (ref "T25") (pin "1") (pinfunction "Test_Point_1") (pintype "passive"))
    )
    (net (code "28") (name "/IO_TP_2") (class "Default")
      (node (ref "J404") (pin "8") (pinfunction "8_8") (pintype "passive"))
      (node (ref "T24") (pin "1") (pinfunction "Test_Point_1") (pintype "passive"))
    )
    (net (code "29") (name "3V") (class "Default")
      (node (ref "J404") (pin "2") (pinfunction "2_2") (pintype "passive"))
      (node (ref "T27") (pin "1") (pinfunction "Test_Point_1") (pintype "passive"))
    )
    (net (code "30") (name "GND") (class "Default")
      (node (ref "C401") (pin "1") (pinfunction "1_1") (pintype "passive"))
      (node (ref "C402") (pin "1") (pinfunction "1_1") (pintype "passive"))
      (node (ref "C403") (pin "1") (pinfunction "1_1") (pintype "passive"))
      (node (ref "C404") (pin "1") (pinfunction "1_1") (pintype "passive"))
      (node (ref "C405") (pin "1") (pinfunction "1_1") (pintype "passive"))
      (node (ref "J401") (pin "10") (pinfunction "10_10") (pintype "passive"))
      (node (ref "J401") (pin "SH") (pinfunction "SH_SH") (pintype "passive"))
      (node (ref "J402") (pin "10") (pinfunction "10_10") (pintype "passive"))
      (node (ref "J402") (pin "SH") (pinfunction "SH_SH") (pintype "passive"))
      (node (ref "J403") (pin "10") (pinfunction "10_10") (pintype "passive"))
      (node (ref "J403") (pin "SH") (pinfunction "SH_SH") (pintype "passive"))
      (node (ref "J404") (pin "1") (pinfunction "1_1") (pintype "passive"))
      (node (ref "J404") (pin "SH") (pinfunction "SH_SH") (pintype "passive"))
      (node (ref "J405") (pin "10") (pinfunction "10_10") (pintype "passive"))
      (node (ref "J405") (pin "SH") (pinfunction "SH_SH") (pintype "passive"))
      (node (ref "J406") (pin "10") (pinfunction "10_10") (pintype "passive"))
      (node (ref "J406") (pin "SH") (pinfunction "SH_SH") (pintype "passive"))
      (node (ref "R407") (pin "2") (pintype "passive"))
      (node (ref "R411") (pin "2") (pintype "passive"))
      (node (ref "R424") (pin "2") (pintype "passive"))
      (node (ref "R425") (pin "2") (pintype "passive"))
      (node (ref "R426") (pin "1") (pintype "passive"))
      (node (ref "R427") (pin "1") (pintype "passive"))
      (node (ref "R428") (pin "2") (pintype "passive"))
      (node (ref "R429") (pin "1") (pintype "passive"))
      (node (ref "R434") (pin "2") (pintype "passive"))
      (node (ref "R438") (pin "2") (pintype "passive"))
      (node (ref "R448") (pin "2") (pintype "passive"))
      (node (ref "R450") (pin "1") (pintype "passive"))
      (node (ref "R451") (pin "2") (pintype "passive"))
      (node (ref "R452") (pin "1") (pintype "passive"))
      (node (ref "TP421") (pin "1") (pinfunction "8_1") (pintype "passive"))
      (node (ref "TP422") (pin "1") (pinfunction "8_1") (pintype "passive"))
      (node (ref "TP424") (pin "1") (pinfunction "8_1") (pintype "passive"))
      (node (ref "TP440") (pin "1") (pinfunction "8_1") (pintype "passive"))
      (node (ref "TP443") (pin "1") (pinfunction "8_1") (pintype "passive"))
      (node (ref "U401") (pin "3") (pinfunction "GND_3") (pintype "passive"))
      (node (ref "U401") (pin "4") (pinfunction "GND_4") (pintype "passive"))
    )
    (net (code "31") (name "Net-(D401-A)") (class "Default")
      (node (ref "D401") (pin "1") (pinfunction "A_1") (pintype "passive"))
      (node (ref "R402") (pin "1") (pintype "passive"))
      (node (ref "TP407") (pin "1") (pintype "power_in"))
    )
    (net (code "32") (name "Net-(D401-C)") (class "Default")
      (node (ref "D401") (pin "2") (pinfunction "C_2") (pintype "passive"))
      (node (ref "R415") (pin "1") (pintype "passive"))
      (node (ref "T7") (pin "1") (pinfunction "Test_Point_1") (pintype "passive"))
    )
    (net (code "33") (name "Net-(D402-A)") (class "Default")
      (node (ref "D402") (pin "1") (pinfunction "A_1") (pintype "passive"))
      (node (ref "R404") (pin "1") (pintype "passive"))
      (node (ref "TP408") (pin "1") (pintype "power_in"))
    )
    (net (code "34") (name "Net-(D402-K)") (class "Default")
      (node (ref "D402") (pin "2") (pinfunction "K_2") (pintype "passive"))
      (node (ref "R416") (pin "1") (pintype "passive"))
      (node (ref "T8") (pin "1") (pinfunction "Test_Point_1") (pintype "passive"))
    )
    (net (code "35") (name "Net-(D403-A)") (class "Default")
      (node (ref "D403") (pin "2") (pinfunction "A_2") (pintype "passive"))
      (node (ref "R406") (pin "1") (pintype "passive"))
      (node (ref "TP409") (pin "1") (pintype "power_in"))
    )
    (net (code "36") (name "Net-(D403-C)") (class "Default")
      (node (ref "D403") (pin "1") (pinfunction "C_1") (pintype "passive"))
      (node (ref "R417") (pin "1") (pintype "passive"))
      (node (ref "T9") (pin "1") (pinfunction "Test_Point_1") (pintype "passive"))
    )
    (net (code "37") (name "Net-(D404-A)") (class "Default")
      (node (ref "D404") (pin "2") (pinfunction "A_2") (pintype "passive"))
      (node (ref "R430") (pin "1") (pintype "passive"))
      (node (ref "TP429") (pin "1") (pintype "power_in"))
    )
    (net (code "38") (name "Net-(D404-C)") (class "Default")
      (node (ref "D404") (pin "1") (pinfunction "C_1") (pintype "passive"))
      (node (ref "R442") (pin "1") (pintype "passive"))
      (node (ref "T19") (pin "1") (pinfunction "Test_Point_1") (pintype "passive"))
    )
    (net (code "39") (name "Net-(D405-PadA)") (class "Default")
      (node (ref "D405") (pin "A") (pinfunction "A_A") (pintype "passive"))
      (node (ref "R432") (pin "1") (pintype "passive"))
      (node (ref "TP430") (pin "1") (pintype "power_in"))
    )
    (net (code "40") (name "Net-(J401-Pad2)") (class "Default")
      (node (ref "J401") (pin "2") (pinfunction "2_2") (pintype "passive"))
      (node (ref "R410") (pin "2") (pintype "passive"))
    )
    (net (code "41") (name "Net-(J401-Pad3)") (class "Default")
      (node (ref "J401") (pin "3") (pinfunction "3_3") (pintype "passive"))
      (node (ref "R409") (pin "2") (pintype "passive"))
    )
    (net (code "42") (name "Net-(J401-Pad4)") (class "Default")
      (node (ref "J401") (pin "4") (pinfunction "4_4") (pintype "passive"))
      (node (ref "R408") (pin "2") (pintype "passive"))
    )
    (net (code "43") (name "Net-(J402-Pad2)") (class "Default")
      (node (ref "J402") (pin "2") (pinfunction "2_2") (pintype "passive"))
      (node (ref "R414") (pin "2") (pintype "passive"))
    )
    (net (code "44") (name "Net-(J402-Pad3)") (class "Default")
      (node (ref "J402") (pin "3") (pinfunction "3_3") (pintype "passive"))
      (node (ref "R413") (pin "2") (pintype "passive"))
    )
    (net (code "45") (name "Net-(J402-Pad4)") (class "Default")
      (node (ref "J402") (pin "4") (pinfunction "4_4") (pintype "passive"))
      (node (ref "R412") (pin "2") (pintype "passive"))
    )
    (net (code "46") (name "Net-(J405-Pad2)") (class "Default")
      (node (ref "J405") (pin "2") (pinfunction "2_2") (pintype "passive"))
      (node (ref "R437") (pin "2") (pintype "passive"))
    )
    (net (code "47") (name "Net-(J405-Pad3)") (class "Default")
      (node (ref "J405") (pin "3") (pinfunction "3_3") (pintype "passive"))
      (node (ref "R436") (pin "2") (pintype "passive"))
    )
    (net (code "48") (name "Net-(J405-Pad4)") (class "Default")
      (node (ref "J405") (pin "4") (pinfunction "4_4") (pintype "passive"))
      (node (ref "R435") (pin "2") (pintype "passive"))
    )
    (net (code "49") (name "Net-(J406-Pad2)") (class "Default")
      (node (ref "J406") (pin "2") (pinfunction "2_2") (pintype "passive"))
      (node (ref "R441") (pin "2") (pintype "passive"))
    )
    (net (code "50") (name "Net-(J406-Pad3)") (class "Default")
      (node (ref "J406") (pin "3") (pinfunction "3_3") (pintype "passive"))
      (node (ref "R440") (pin "2") (pintype "passive"))
    )
    (net (code "51") (name "Net-(J406-Pad4)") (class "Default")
      (node (ref "J406") (pin "4") (pinfunction "4_4") (pintype "passive"))
      (node (ref "R439") (pin "2") (pintype "passive"))
    )
    (net (code "52") (name "Net-(Q401-PadE)") (class "Default")
      (node (ref "Q401") (pin "E") (pinfunction "E_E") (pintype "passive"))
      (node (ref "R454") (pin "1") (pintype "passive"))
    )
    (net (code "53") (name "Net-(Q402-C)") (class "Default")
      (node (ref "Q402") (pin "2") (pinfunction "C_2") (pintype "passive"))
      (node (ref "R405") (pin "1") (pintype "passive"))
      (node (ref "T3") (pin "1") (pinfunction "Test_Point_1") (pintype "passive"))
      (node (ref "TP404") (pin "1") (pintype "power_in"))
    )
    (net (code "54") (name "Net-(Q402-E)") (class "Default")
      (node (ref "Q402") (pin "1") (pinfunction "E_1") (pintype "passive"))
      (node (ref "R453") (pin "1") (pintype "passive"))
    )
    (net (code "55") (name "Net-(Q403-1)") (class "Default")
      (node (ref "Q403") (pin "G") (pinfunction "1_G") (pintype "passive"))
      (node (ref "R421") (pin "2") (pintype "passive"))
    )
    (net (code "56") (name "Net-(Q403-2)") (class "Default")
      (node (ref "Q403") (pin "S") (pinfunction "2_S") (pintype "passive"))
      (node (ref "R426") (pin "2") (pintype "passive"))
    )
    (net (code "57") (name "Net-(Q403-3)") (class "Default")
      (node (ref "Q403") (pin "D") (pinfunction "3_D") (pintype "passive"))
      (node (ref "R418") (pin "2") (pintype "passive"))
    )
    (net (code "58") (name "Net-(Q404-1)") (class "Default")
      (node (ref "Q404") (pin "G") (pinfunction "1_G") (pintype "passive"))
      (node (ref "R422") (pin "2") (pintype "passive"))
    )
    (net (code "59") (name "Net-(Q404-2)") (class "Default")
      (node (ref "Q404") (pin "S") (pinfunction "2_S") (pintype "passive"))
      (node (ref "R427") (pin "2") (pintype "passive"))
    )
    (net (code "60") (name "Net-(Q404-3)") (class "Default")
      (node (ref "Q404") (pin "D") (pinfunction "3_D") (pintype "passive"))
      (node (ref "R419") (pin "2") (pintype "passive"))
    )
    (net (code "61") (name "Net-(Q405-1)") (class "Default")
      (node (ref "Q405") (pin "G") (pinfunction "1_G") (pintype "passive"))
      (node (ref "R423") (pin "2") (pintype "passive"))
    )
    (net (code "62") (name "Net-(Q405-2)") (class "Default")
      (node (ref "Q405") (pin "S") (pinfunction "2_S") (pintype "passive"))
      (node (ref "R429") (pin "2") (pintype "passive"))
    )
    (net (code "63") (name "Net-(Q405-3)") (class "Default")
      (node (ref "Q405") (pin "D") (pinfunction "3_D") (pintype "passive"))
      (node (ref "R420") (pin "2") (pintype "passive"))
    )
    (net (code "64") (name "Net-(Q406-C)") (class "Default")
      (node (ref "Q406") (pin "1") (pinfunction "C_1") (pintype "passive"))
      (node (ref "R431") (pin "1") (pintype "passive"))
      (node (ref "T16") (pin "1") (pinfunction "Test_Point_1") (pintype "passive"))
      (node (ref "TP425") (pin "1") (pintype "power_in"))
    )
    (net (code "65") (name "Net-(Q406-E)") (class "Default")
      (node (ref "Q406") (pin "2") (pinfunction "E_2") (pintype "passive"))
      (node (ref "R455") (pin "1") (pintype "passive"))
    )
    (net (code "66") (name "Net-(Q407-PadE)") (class "Default")
      (node (ref "Q407") (pin "E") (pinfunction "E_E") (pintype "passive"))
      (node (ref "R456") (pin "1") (pintype "passive"))
    )
    (net (code "67") (name "Net-(Q408-1)") (class "Default")
      (node (ref "Q408") (pin "G") (pinfunction "1_G") (pintype "passive"))
      (node (ref "R446") (pin "2") (pintype "passive"))
    )
    (net (code "68") (name "Net-(Q408-2)") (class "Default")
      (node (ref "Q408") (pin "S") (pinfunction "2_S") (pintype "passive"))
      (node (ref "R450") (pin "2") (pintype "passive"))
    )
    (net (code "69") (name "Net-(Q408-3)") (class "Default")
      (node (ref "Q408") (pin "D") (pinfunction "3_D") (pintype "passive"))
      (node (ref "R444") (pin "2") (pintype "passive"))
    )
    (net (code "70") (name "Net-(Q409-1)") (class "Default")
      (node (ref "Q409") (pin "G") (pinfunction "1_G") (pintype "passive"))
      (node (ref "R447") (pin "2") (pintype "passive"))
    )
    (net (code "71") (name "Net-(Q409-2)") (class "Default")
      (node (ref "Q409") (pin "S") (pinfunction "2_S") (pintype "passive"))
      (node (ref "R452") (pin "2") (pintype "passive"))
    )
    (net (code "72") (name "Net-(Q409-3)") (class "Default")
      (node (ref "Q409") (pin "D") (pinfunction "3_D") (pintype "passive"))
      (node (ref "R445") (pin "2") (pintype "passive"))
    )
    (net (code "73") (name "Net-(R415-Pad2)") (class "Default")
      (node (ref "R415") (pin "2") (pintype "passive"))
      (node (ref "R418") (pin "1") (pintype "passive"))
    )
    (net (code "74") (name "Net-(R416-Pad2)") (class "Default")
      (node (ref "R416") (pin "2") (pintype "passive"))
      (node (ref "R419") (pin "1") (pintype "passive"))
    )
    (net (code "75") (name "Net-(R417-Pad2)") (class "Default")
      (node (ref "R417") (pin "2") (pintype "passive"))
      (node (ref "R420") (pin "1") (pintype "passive"))
    )
    (net (code "76") (name "Net-(R442-Pad2)") (class "Default")
      (node (ref "R442") (pin "2") (pintype "passive"))
      (node (ref "R444") (pin "1") (pintype "passive"))
    )
    (net (code "77") (name "Net-(R443-Pad2)") (class "Default")
      (node (ref "R443") (pin "2") (pintype "passive"))
      (node (ref "R445") (pin "1") (pintype "passive"))
    )
    (net (code "78") (name "Net-(T1-Test_Point)") (class "Default")
      (node (ref "Q401") (pin "C") (pinfunction "C_C") (pintype "passive"))
      (node (ref "R403") (pin "1") (pintype "passive"))
      (node (ref "T1") (pin "1") (pinfunction "Test_Point_1") (pintype "passive"))
      (node (ref "TP403") (pin "1") (pintype "power_in"))
    )
    (net (code "79") (name "Net-(T2-Test_Point)") (class "Default")
      (node (ref "R401") (pin "1") (pintype "passive"))
      (node (ref "T2") (pin "1") (pinfunction "Test_Point_1") (pintype "passive"))
      (node (ref "TP401") (pin "1") (pintype "power_in"))
      (node (ref "U401") (pin "2") (pinfunction "VS_2") (pintype "passive"))
    )
    (net (code "80") (name "Net-(T10-Test_Point)") (class "Default")
      (node (ref "J403") (pin "2") (pinfunction "2_2") (pintype "passive"))
      (node (ref "T10") (pin "1") (pinfunction "Test_Point_1") (pintype "passive"))
    )
    (net (code "81") (name "Net-(T11-Test_Point)") (class "Default")
      (node (ref "J403") (pin "3") (pinfunction "3_3") (pintype "passive"))
      (node (ref "T11") (pin "1") (pinfunction "Test_Point_1") (pintype "passive"))
    )
    (net (code "82") (name "Net-(T12-Test_Point)") (class "Default")
      (node (ref "J403") (pin "4") (pinfunction "4_4") (pintype "passive"))
      (node (ref "T12") (pin "1") (pinfunction "Test_Point_1") (pintype "passive"))
    )
    (net (code "83") (name "Net-(T17-Test_Point)") (class "Default")
      (node (ref "Q407") (pin "C") (pinfunction "C_C") (pintype "passive"))
      (node (ref "R433") (pin "1") (pintype "passive"))
      (node (ref "T17") (pin "1") (pinfunction "Test_Point_1") (pintype "passive"))
      (node (ref "TP427") (pin "1") (pintype "power_in"))
    )
    (net (code "84") (name "Net-(T21-Test_Point)") (class "Default")
      (node (ref "D405") (pin "C") (pinfunction "C_C") (pintype "passive"))
      (node (ref "R443") (pin "1") (pintype "passive"))
      (node (ref "T21") (pin "1") (pinfunction "Test_Point_1") (pintype "passive"))
    )
    (net (code "85") (name "unconnected-(J401-Pad1)") (class "Default")
      (node (ref "J401") (pin "1") (pinfunction "1_1") (pintype "passive+no_connect"))
    )
    (net (code "86") (name "unconnected-(J401-Pad8)") (class "Default")
      (node (ref "J401") (pin "8") (pinfunction "8_8") (pintype "passive+no_connect"))
    )
    (net (code "87") (name "unconnected-(J402-Pad1)") (class "Default")
      (node (ref "J402") (pin "1") (pinfunction "1_1") (pintype "passive+no_connect"))
    )
    (net (code "88") (name "unconnected-(J402-Pad8)") (class "Default")
      (node (ref "J402") (pin "8") (pinfunction "8_8") (pintype "passive+no_connect"))
    )
    (net (code "89") (name "unconnected-(J403-Pad1)") (class "Default")
      (node (ref "J403") (pin "1") (pinfunction "1_1") (pintype "passive+no_connect"))
    )
    (net (code "90") (name "unconnected-(J403-Pad8)") (class "Default")
      (node (ref "J403") (pin "8") (pinfunction "8_8") (pintype "passive+no_connect"))
    )
    (net (code "91") (name "unconnected-(J405-Pad1)") (class "Default")
      (node (ref "J405") (pin "1") (pinfunction "1_1") (pintype "passive+no_connect"))
    )
    (net (code "92") (name "unconnected-(J405-Pad8)") (class "Default")
      (node (ref "J405") (pin "8") (pinfunction "8_8") (pintype "passive+no_connect"))
    )
    (net (code "93") (name "unconnected-(J406-Pad1)") (class "Default")
      (node (ref "J406") (pin "1") (pinfunction "1_1") (pintype "passive+no_connect"))
    )
    (net (code "94") (name "unconnected-(J406-Pad8)") (class "Default")
      (node (ref "J406") (pin "8") (pinfunction "8_8") (pintype "passive+no_connect"))
    )
  )
)
